# FRONTPANEL.net
KiCad netlist of a schematic drawn in Altium Designer
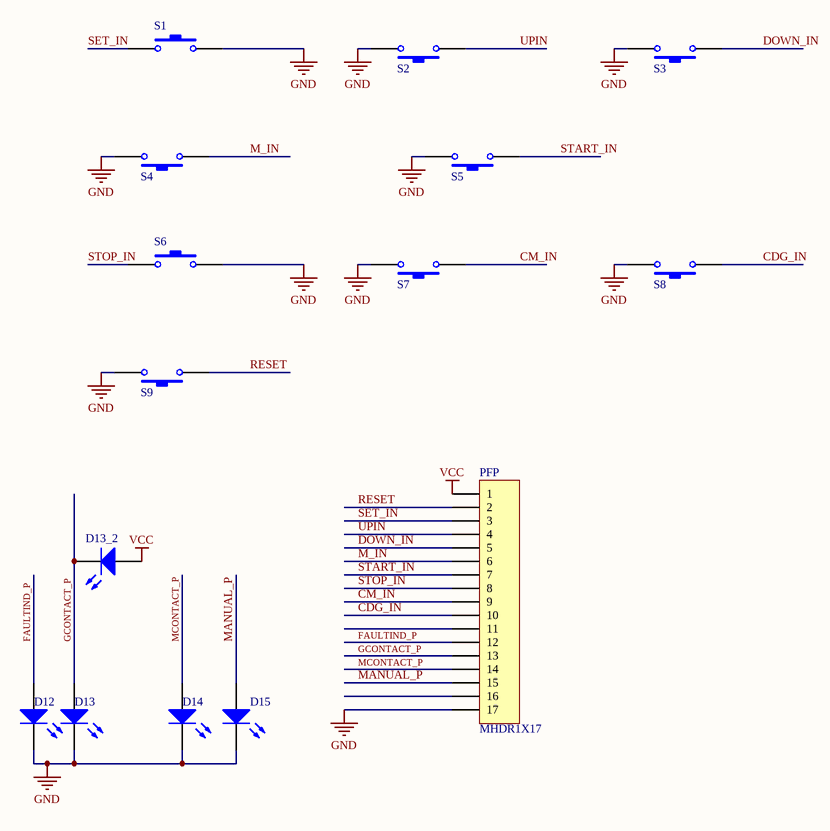
[diagram p0: FRONTPANEL.SchDoc]

(export (version "E")
  (design (tool "Eeschema 10.0.6"))
  (components
    (comp (ref "D12")
      (value "RED LED 3MM")
      (footprint "LEDSMALL")
      (description "3mm LED")
      (fields (field (name "PUBLISHER") "Altium Limited"))
      (libsource (lib "Miscellaneous Devices") (part "LED1"))
    )
    (comp (ref "D13")
      (value "GREEN LED 3MM")
      (footprint "LEDSMALL")
      (description "3mm LED")
      (fields (field (name "PUBLISHER") "Altium Limited"))
      (libsource (lib "Miscellaneous Devices") (part "LED1"))
    )
    (comp (ref "D13_2")
      (value "GREEN LED 3MM")
      (footprint "LEDSMALL")
      (description "3mm LED")
      (fields (field (name "PUBLISHER") "Altium Limited"))
      (libsource (lib "Miscellaneous Devices") (part "LED1"))
    )
    (comp (ref "D14")
      (value "GREEN LED 3MM")
      (footprint "LEDSMALL")
      (description "3mm LED")
      (fields (field (name "PUBLISHER") "Altium Limited"))
      (libsource (lib "Miscellaneous Devices") (part "LED1"))
    )
    (comp (ref "D15")
      (value "YELLOW LED 3MM")
      (footprint "LEDSMALL")
      (description "3mm LED")
      (fields (field (name "PUBLISHER") "Altium Limited"))
      (libsource (lib "Miscellaneous Devices") (part "LED1"))
    )
    (comp (ref "PFP")
      (value "MHDR1X17")
      (footprint "HDR1X17_BURGE_M_ST")
      (description "Header, 17-Pin")
      (fields (field (name "PUBLISHER") "Altium Limited"))
      (libsource (lib "Miscellaneous Connectors") (part "MHDR1X17"))
    )
    (comp (ref "S1")
      (value "8MM DOM SWITCH")
      (footprint "DOMKEY8MM")
      (description "Switch")
      (fields (field (name "PUBLISHER") "Altium Limited"))
      (libsource (lib "Miscellaneous Devices") (part "SW-PB"))
    )
    (comp (ref "S2")
      (value "8MM DOM SWITCH")
      (footprint "DOMKEY8MM")
      (description "Switch")
      (fields (field (name "PUBLISHER") "Altium Limited"))
      (libsource (lib "Miscellaneous Devices") (part "SW-PB"))
    )
    (comp (ref "S3")
      (value "8MM DOM SWITCH")
      (footprint "DOMKEY8MM")
      (description "Switch")
      (fields (field (name "PUBLISHER") "Altium Limited"))
      (libsource (lib "Miscellaneous Devices") (part "SW-PB"))
    )
    (comp (ref "S4")
      (value "8MM DOM SWITCH")
      (footprint "DOMKEY8MM")
      (description "Switch")
      (fields (field (name "PUBLISHER") "Altium Limited"))
      (libsource (lib "Miscellaneous Devices") (part "SW-PB"))
    )
    (comp (ref "S5")
      (value "8MM DOM SWITCH")
      (footprint "DOMKEY8MM")
      (description "Switch")
      (fields (field (name "PUBLISHER") "Altium Limited"))
      (libsource (lib "Miscellaneous Devices") (part "SW-PB"))
    )
    (comp (ref "S6")
      (value "8MM DOM SWITCH")
      (footprint "DOMKEY8MM")
      (description "Switch")
      (fields (field (name "PUBLISHER") "Altium Limited"))
      (libsource (lib "Miscellaneous Devices") (part "SW-PB"))
    )
    (comp (ref "S7")
      (value "8MM DOM SWITCH")
      (footprint "DOMKEY8MM")
      (description "Switch")
      (fields (field (name "PUBLISHER") "Altium Limited"))
      (libsource (lib "Miscellaneous Devices") (part "SW-PB"))
    )
    (comp (ref "S8")
      (value "8MM DOM SWITCH")
      (footprint "DOMKEY8MM")
      (description "Switch")
      (fields (field (name "PUBLISHER") "Altium Limited"))
      (libsource (lib "Miscellaneous Devices") (part "SW-PB"))
    )
    (comp (ref "S9")
      (value "8MM DOM SWITCH")
      (footprint "DOMKEY8MM")
      (description "Switch")
      (fields (field (name "PUBLISHER") "Altium Limited"))
      (libsource (lib "Miscellaneous Devices") (part "SW-PB"))
    )
  )
  (nets
    (net (code "1") (name "/CDG_IN") (class "Default")
      (node (ref "PFP") (pin "10") (pinfunction "10_10") (pintype "passive"))
      (node (ref "S8") (pin "1") (pinfunction "1_1") (pintype "passive"))
    )
    (net (code "2") (name "/CM_IN") (class "Default")
      (node (ref "PFP") (pin "9") (pinfunction "9_9") (pintype "passive"))
      (node (ref "S7") (pin "1") (pinfunction "1_1") (pintype "passive"))
    )
    (net (code "3") (name "/DOWN_IN") (class "Default")
      (node (ref "PFP") (pin "5") (pinfunction "5_5") (pintype "passive"))
      (node (ref "S3") (pin "1") (pinfunction "1_1") (pintype "passive"))
    )
    (net (code "4") (name "/FAULTIND_P") (class "Default")
      (node (ref "D12") (pin "1") (pinfunction "A_1") (pintype "passive"))
      (node (ref "PFP") (pin "12") (pinfunction "12_12") (pintype "passive"))
    )
    (net (code "5") (name "/GCONTACT_P") (class "Default")
      (node (ref "D13") (pin "1") (pinfunction "A_1") (pintype "passive"))
      (node (ref "D13_2") (pin "2") (pinfunction "K_2") (pintype "passive"))
      (node (ref "PFP") (pin "13") (pinfunction "13_13") (pintype "passive"))
    )
    (net (code "6") (name "/MANUAL_P") (class "Default")
      (node (ref "D15") (pin "1") (pinfunction "A_1") (pintype "passive"))
      (node (ref "PFP") (pin "15") (pinfunction "15_15") (pintype "passive"))
    )
    (net (code "7") (name "/MCONTACT_P") (class "Default")
      (node (ref "D14") (pin "1") (pinfunction "A_1") (pintype "passive"))
      (node (ref "PFP") (pin "14") (pinfunction "14_14") (pintype "passive"))
    )
    (net (code "8") (name "/M_IN") (class "Default")
      (node (ref "PFP") (pin "6") (pinfunction "6_6") (pintype "passive"))
      (node (ref "S4") (pin "1") (pinfunction "1_1") (pintype "passive"))
    )
    (net (code "9") (name "/RESET") (class "Default")
      (node (ref "PFP") (pin "2") (pinfunction "2_2") (pintype "passive"))
      (node (ref "S9") (pin "1") (pinfunction "1_1") (pintype "passive"))
    )
    (net (code "10") (name "/SET_IN") (class "Default")
      (node (ref "PFP") (pin "3") (pinfunction "3_3") (pintype "passive"))
      (node (ref "S1") (pin "1") (pinfunction "1_1") (pintype "passive"))
    )
    (net (code "11") (name "/START_IN") (class "Default")
      (node (ref "PFP") (pin "7") (pinfunction "7_7") (pintype "passive"))
      (node (ref "S5") (pin "1") (pinfunction "1_1") (pintype "passive"))
    )
    (net (code "12") (name "/STOP_IN") (class "Default")
      (node (ref "PFP") (pin "8") (pinfunction "8_8") (pintype "passive"))
      (node (ref "S6") (pin "1") (pinfunction "1_1") (pintype "passive"))
    )
    (net (code "13") (name "/UPIN") (class "Default")
      (node (ref "PFP") (pin "4") (pinfunction "4_4") (pintype "passive"))
      (node (ref "S2") (pin "1") (pinfunction "1_1") (pintype "passive"))
    )
    (net (code "14") (name "GND") (class "Default")
      (node (ref "D12") (pin "2") (pinfunction "K_2") (pintype "passive"))
      (node (ref "D13") (pin "2") (pinfunction "K_2") (pintype "passive"))
      (node (ref "D14") (pin "2") (pinfunction "K_2") (pintype "passive"))
      (node (ref "D15") (pin "2") (pinfunction "K_2") (pintype "passive"))
      (node (ref "PFP") (pin "17") (pinfunction "17_17") (pintype "passive"))
      (node (ref "S1") (pin "2") (pinfunction "2_2") (pintype "passive"))
      (node (ref "S2") (pin "2") (pinfunction "2_2") (pintype "passive"))
      (node (ref "S3") (pin "2") (pinfunction "2_2") (pintype "passive"))
      (node (ref "S4") (pin "2") (pinfunction "2_2") (pintype "passive"))
      (node (ref "S5") (pin "2") (pinfunction "2_2") (pintype "passive"))
      (node (ref "S6") (pin "2") (pinfunction "2_2") (pintype "passive"))
      (node (ref "S7") (pin "2") (pinfunction "2_2") (pintype "passive"))
      (node (ref "S8") (pin "2") (pinfunction "2_2") (pintype "passive"))
      (node (ref "S9") (pin "2") (pinfunction "2_2") (pintype "passive"))
    )
    (net (code "15") (name "VCC") (class "Default")
      (node (ref "D13_2") (pin "1") (pinfunction "A_1") (pintype "passive"))
      (node (ref "PFP") (pin "1") (pinfunction "1_1") (pintype "passive"))
    )
    (net (code "16") (name "unconnected-(PFP-Pad11)") (class "Default")
      (node (ref "PFP") (pin "11") (pinfunction "11_11") (pintype "passive"))
    )
    (net (code "17") (name "unconnected-(PFP-Pad16)") (class "Default")
      (node (ref "PFP") (pin "16") (pinfunction "16_16") (pintype "passive"))
    )
  )
)
